# panelize.net
KiCad netlist of a schematic drawn in EAGLE
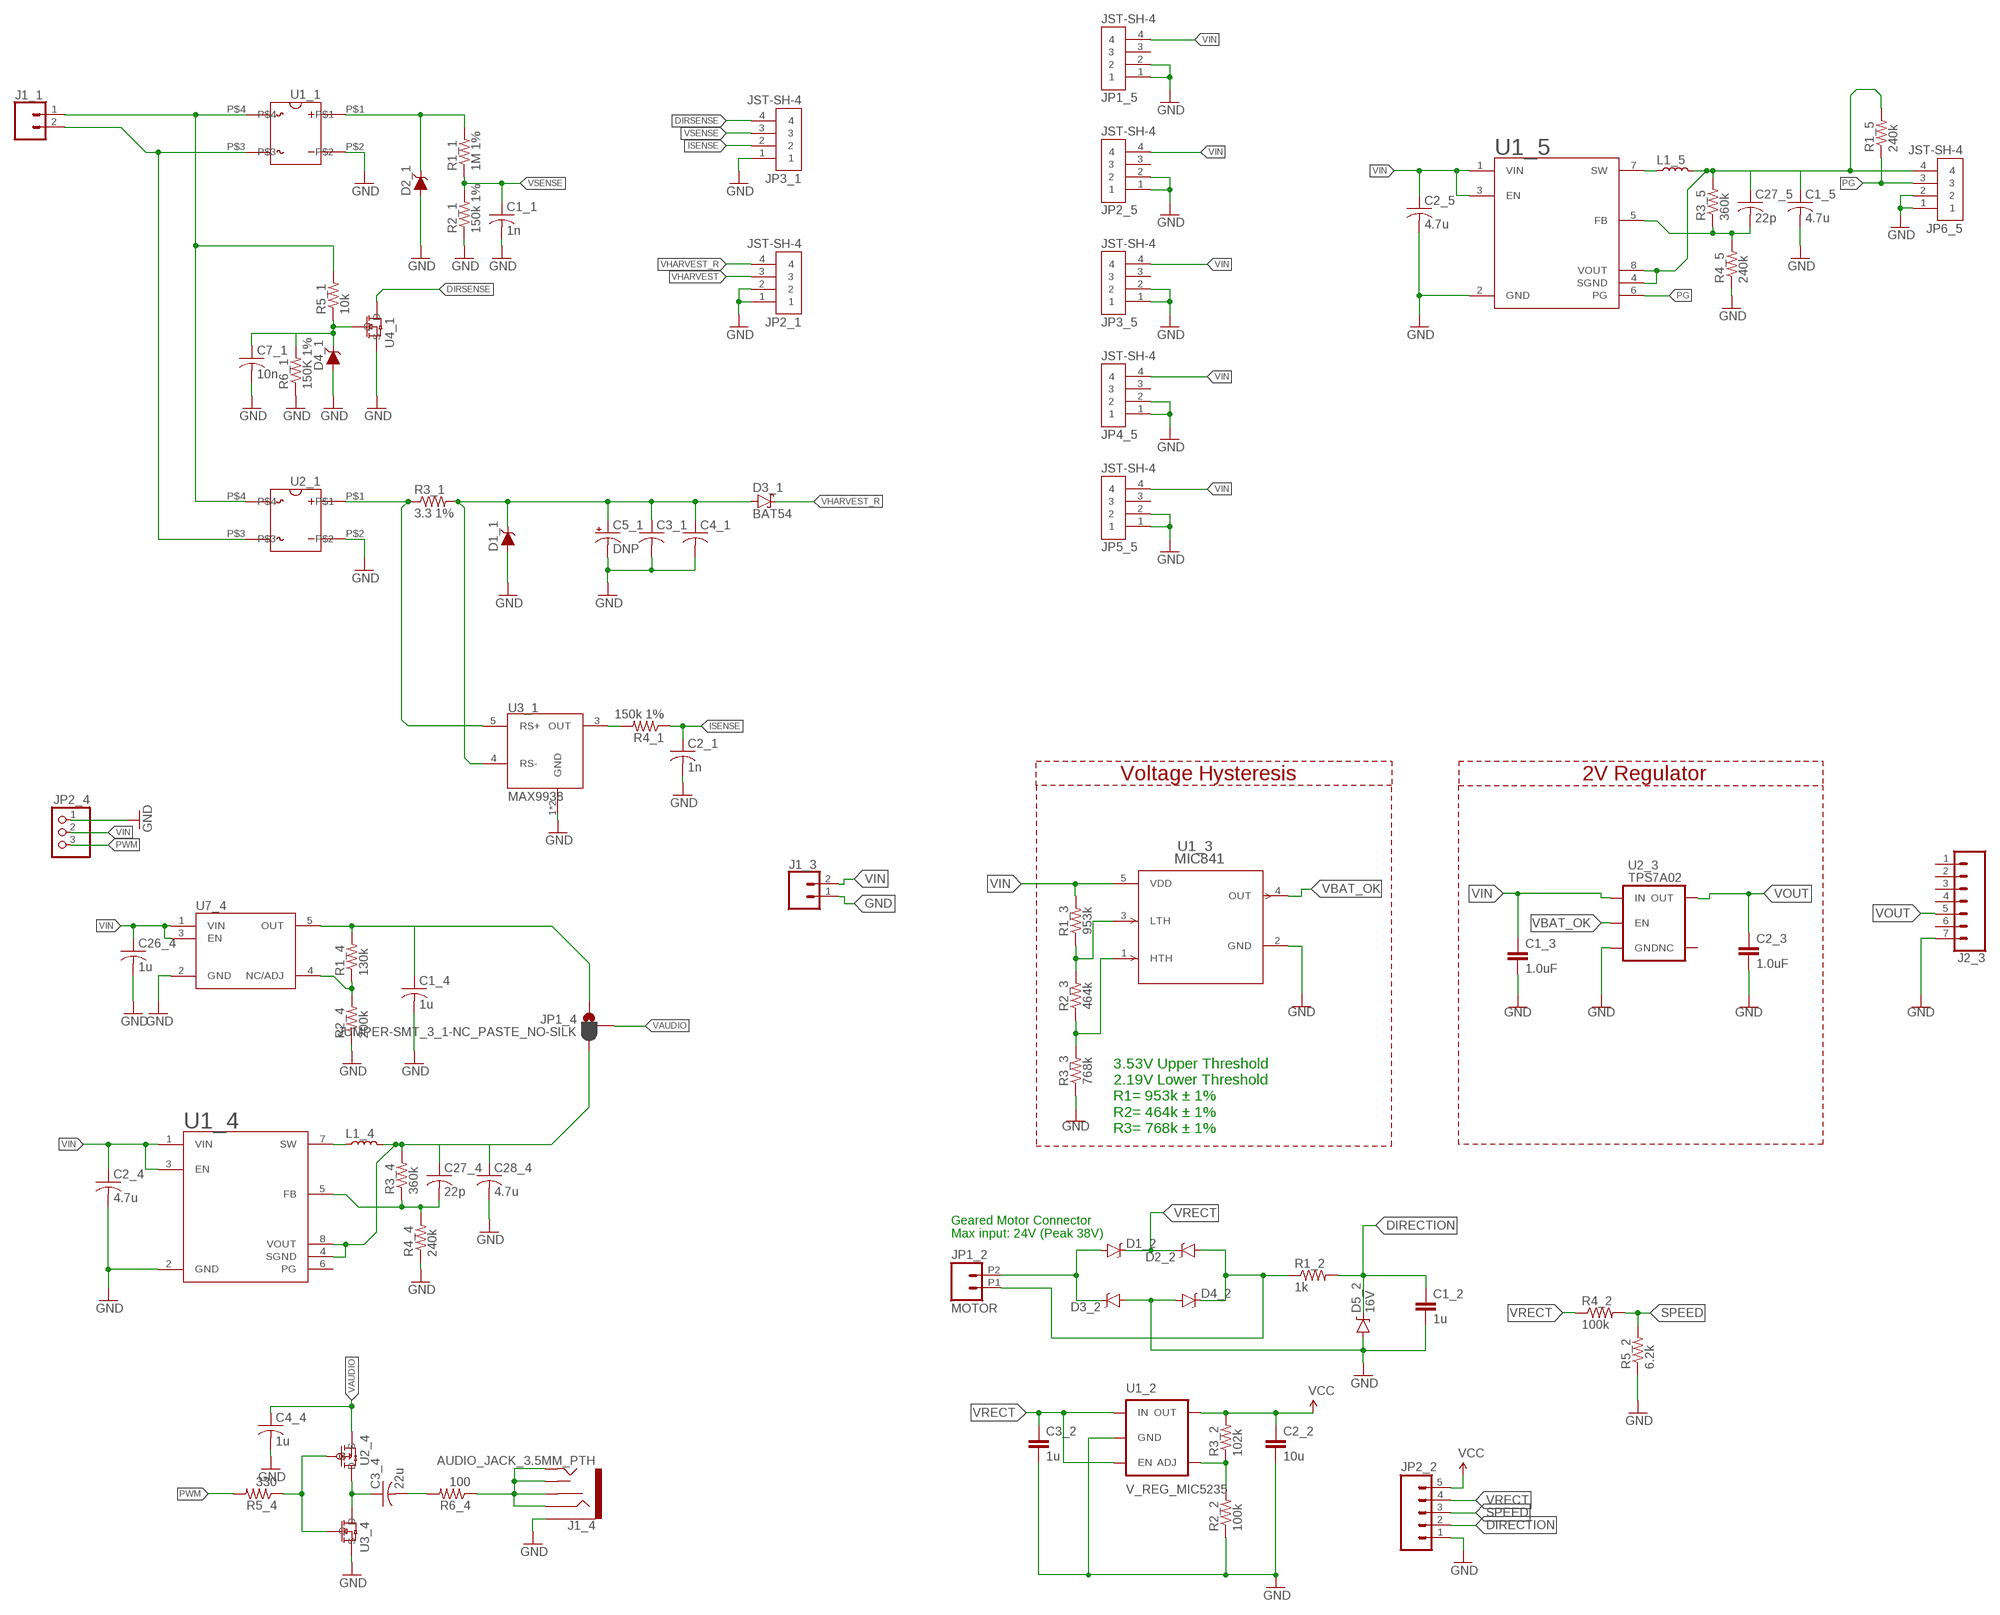
[diagram p0: schematic, sheet 1]

(export (version "E")
  (design (tool "Eeschema 10.0.6"))
  (components
    (comp (ref "C1_1")
      (value "1n")
      (footprint "eagle-import:C0402")
      (fields (field (name "MFR") "SAMSUNG"))
      (libsource (lib "eagle-import") (part "C-USC0402"))
    )
    (comp (ref "C1_2")
      (value "1u")
      (footprint "eagle-import:0805")
      (libsource (lib "eagle-import") (part "CAP0805"))
    )
    (comp (ref "C1_3")
      (value "1.0uF")
      (footprint "eagle-import:0603")
      (fields (field (name "MFR") "SAMSUNG"))
      (libsource (lib "eagle-import") (part "1.0UF-0603-16V-10%"))
    )
    (comp (ref "C1_4")
      (value "1u")
      (footprint "eagle-import:C0603")
      (fields (field (name "MFR") "SAMSUNG"))
      (libsource (lib "eagle-import") (part "C-USC0603"))
    )
    (comp (ref "C1_5")
      (value "4.7u")
      (footprint "eagle-import:C0603")
      (fields (field (name "MFR") "SAMSUNG"))
      (libsource (lib "eagle-import") (part "C-USC0603"))
    )
    (comp (ref "C2_1")
      (value "1n")
      (footprint "eagle-import:C0402")
      (fields (field (name "MFR") "SAMSUNG"))
      (libsource (lib "eagle-import") (part "C-USC0402"))
    )
    (comp (ref "C2_2")
      (value "10u")
      (footprint "eagle-import:0805")
      (libsource (lib "eagle-import") (part "CAP0805"))
    )
    (comp (ref "C2_3")
      (value "1.0uF")
      (footprint "eagle-import:0603")
      (fields (field (name "MFR") "SAMSUNG"))
      (libsource (lib "eagle-import") (part "1.0UF-0603-16V-10%"))
    )
    (comp (ref "C2_4")
      (value "4.7u")
      (footprint "eagle-import:C0603")
      (fields (field (name "MFR") "SAMSUNG"))
      (libsource (lib "eagle-import") (part "C-USC0603"))
    )
    (comp (ref "C2_5")
      (value "4.7u")
      (footprint "eagle-import:C0603")
      (fields (field (name "MFR") "SAMSUNG"))
      (libsource (lib "eagle-import") (part "C-USC0603"))
    )
    (comp (ref "C3_1")
      (value "C-USC1206")
      (footprint "eagle-import:C1206")
      (fields (field (name "MFR") "TDK"))
      (libsource (lib "eagle-import") (part "C-USC1206"))
    )
    (comp (ref "C3_2")
      (value "1u")
      (footprint "eagle-import:0805")
      (libsource (lib "eagle-import") (part "CAP0805"))
    )
    (comp (ref "C3_4")
      (value "22u")
      (footprint "eagle-import:C0805")
      (fields (field (name "MFR") "MURATA"))
      (libsource (lib "eagle-import") (part "C-USC0805"))
    )
    (comp (ref "C4_1")
      (value "C-USC1206")
      (footprint "eagle-import:C1206")
      (fields (field (name "MFR") "TDK"))
      (libsource (lib "eagle-import") (part "C-USC1206"))
    )
    (comp (ref "C4_4")
      (value "1u")
      (footprint "eagle-import:C0603")
      (fields (field (name "MFR") "SAMSUNG"))
      (libsource (lib "eagle-import") (part "C-USC0603"))
    )
    (comp (ref "C5_1")
      (value "DNP")
      (footprint "eagle-import:E2,5-5")
      (libsource (lib "eagle-import") (part "CPOL-USE2.5-5"))
    )
    (comp (ref "C7_1")
      (value "10n")
      (footprint "eagle-import:C0402")
      (fields (field (name "MFR") "SAMSUNG"))
      (libsource (lib "eagle-import") (part "C-USC0402"))
    )
    (comp (ref "C26_4")
      (value "1u")
      (footprint "eagle-import:C0603")
      (fields (field (name "MFR") "SAMSUNG"))
      (libsource (lib "eagle-import") (part "C-USC0603"))
    )
    (comp (ref "C27_4")
      (value "22p")
      (footprint "eagle-import:C0402")
      (fields (field (name "MFR") "KEMET"))
      (libsource (lib "eagle-import") (part "C-USC0402"))
    )
    (comp (ref "C27_5")
      (value "22p")
      (footprint "eagle-import:C0402")
      (fields (field (name "MFR") "KEMET"))
      (libsource (lib "eagle-import") (part "C-USC0402"))
    )
    (comp (ref "C28_4")
      (value "4.7u")
      (footprint "eagle-import:C0603")
      (fields (field (name "MFR") "SAMSUNG"))
      (libsource (lib "eagle-import") (part "C-USC0603"))
    )
    (comp (ref "D1_1")
      (value "3.3V")
      (footprint "eagle-import:SOD-323")
      (fields (field (name "MFR") "DIODES_INCORPORATED"))
      (libsource (lib "eagle-import") (part "DIODE-ZENER-MM3Z3V3T1G"))
    )
    (comp (ref "D1_2")
      (value "BAT20JFILM")
      (footprint "eagle-import:SOD-323")
      (libsource (lib "eagle-import") (part "BAT20JFILM"))
    )
    (comp (ref "D2_1")
      (value "3.3V")
      (footprint "eagle-import:SOD-323")
      (fields (field (name "MFR") "DIODES_INCORPORATED"))
      (libsource (lib "eagle-import") (part "DIODE-ZENER-MM3Z3V3T1G"))
    )
    (comp (ref "D2_2")
      (value "BAT20JFILM")
      (footprint "eagle-import:SOD-323")
      (libsource (lib "eagle-import") (part "BAT20JFILM"))
    )
    (comp (ref "D3_1")
      (value "BAT54")
      (footprint "eagle-import:SOT23")
      (fields (field (name "MFR") "ON"))
      (libsource (lib "eagle-import") (part "BAT54"))
    )
    (comp (ref "D3_2")
      (value "BAT20JFILM")
      (footprint "eagle-import:SOD-323")
      (libsource (lib "eagle-import") (part "BAT20JFILM"))
    )
    (comp (ref "D4_1")
      (value "3.3V")
      (footprint "eagle-import:SOD-323")
      (fields (field (name "MFR") "DIODES_INCORPORATED"))
      (libsource (lib "eagle-import") (part "DIODE-ZENER-MM3Z3V3T1G"))
    )
    (comp (ref "D4_2")
      (value "BAT20JFILM")
      (footprint "eagle-import:SOD-323")
      (libsource (lib "eagle-import") (part "BAT20JFILM"))
    )
    (comp (ref "D5_2")
      (value "16V")
      (footprint "eagle-import:SOD-123")
      (libsource (lib "eagle-import") (part "DIODE-ZENER16V"))
    )
    (comp (ref "J1_1")
      (value "CONN_02-JST-2MM-SMT")
      (footprint "eagle-import:JST-2-SMD")
      (fields (field (name "MFR") "JST"))
      (libsource (lib "eagle-import") (part "SparkFun-Connectors_513_CONN_02-JST-2MM-SMT"))
    )
    (comp (ref "J1_3")
      (value "CONN_02")
      (footprint "eagle-import:1X02")
      (fields (field (name "MFR") "DNP"))
      (libsource (lib "eagle-import") (part "CONN_02"))
    )
    (comp (ref "J1_4")
      (value "AUDIO_JACK_3.5MM_PTH")
      (footprint "eagle-import:AUDIO-JACK")
      (fields (field (name "MFR") "DNP"))
      (libsource (lib "eagle-import") (part "AUDIO_JACK_3.5MM_PTH"))
    )
    (comp (ref "J2_3")
      (value "CONN_07")
      (footprint "eagle-import:1X07")
      (fields (field (name "MFR") "DNP"))
      (libsource (lib "eagle-import") (part "CONN_07"))
    )
    (comp (ref "JP1_2")
      (value "MOTOR")
      (footprint "eagle-import:1X02_2.54_SCREWTERM@1")
      (fields (field (name "MFR") "DNP"))
      (libsource (lib "eagle-import") (part "M022.54MM_SCREWTERM"))
    )
    (comp (ref "JP1_4")
      (value "JUMPER-SMT_3_1-NC_PASTE_NO-SILK")
      (footprint "eagle-import:SMT-JUMPER_3_1-NC_PASTE_NO-SILK")
      (fields (field (name "MFR") "DNP"))
      (libsource (lib "eagle-import") (part "JUMPER-SMT_3_1-NC_PASTE_NO-SILK"))
    )
    (comp (ref "JP1_5")
      (value "JST-SH-4")
      (footprint "eagle-import:JST-SH-4")
      (fields (field (name "MFR") "JST"))
      (libsource (lib "eagle-import") (part "JST-SH-4"))
    )
    (comp (ref "JP2_1")
      (value "JST-SH-4")
      (footprint "eagle-import:JST-SH-4")
      (fields (field (name "MFR") "JST"))
      (libsource (lib "eagle-import") (part "JST-SH-4"))
    )
    (comp (ref "JP2_2")
      (value "M05LOCK")
      (footprint "eagle-import:1X05_LOCK")
      (fields (field (name "MFR") "DNP"))
      (libsource (lib "eagle-import") (part "M05LOCK"))
    )
    (comp (ref "JP2_4")
      (value "PINHD-1X3")
      (footprint "eagle-import:1X03")
      (fields (field (name "MFR") "DNP"))
      (libsource (lib "eagle-import") (part "PINHD-1X3"))
    )
    (comp (ref "JP2_5")
      (value "JST-SH-4")
      (footprint "eagle-import:JST-SH-4")
      (fields (field (name "MFR") "JST"))
      (libsource (lib "eagle-import") (part "JST-SH-4"))
    )
    (comp (ref "JP3_1")
      (value "JST-SH-4")
      (footprint "eagle-import:JST-SH-4")
      (fields (field (name "MFR") "JST"))
      (libsource (lib "eagle-import") (part "JST-SH-4"))
    )
    (comp (ref "JP3_5")
      (value "JST-SH-4")
      (footprint "eagle-import:JST-SH-4")
      (fields (field (name "MFR") "JST"))
      (libsource (lib "eagle-import") (part "JST-SH-4"))
    )
    (comp (ref "JP4_5")
      (value "JST-SH-4")
      (footprint "eagle-import:JST-SH-4")
      (fields (field (name "MFR") "JST"))
      (libsource (lib "eagle-import") (part "JST-SH-4"))
    )
    (comp (ref "JP5_5")
      (value "JST-SH-4")
      (footprint "eagle-import:JST-SH-4")
      (fields (field (name "MFR") "JST"))
      (libsource (lib "eagle-import") (part "JST-SH-4"))
    )
    (comp (ref "JP6_5")
      (value "JST-SH-4")
      (footprint "eagle-import:JST-SH-4")
      (fields (field (name "MFR") "JST"))
      (libsource (lib "eagle-import") (part "JST-SH-4"))
    )
    (comp (ref "L1_4")
      (value "22u")
      (footprint "eagle-import:LQH3NPNXXXXMEX")
      (fields (field (name "MFR") "MURATA"))
      (libsource (lib "eagle-import") (part "LQH3NPN220MMEL"))
    )
    (comp (ref "L1_5")
      (value "22u")
      (footprint "eagle-import:LQH3NPNXXXXMEX")
      (fields (field (name "MFR") "MURATA"))
      (libsource (lib "eagle-import") (part "LQH3NPN220MMEL"))
    )
    (comp (ref "R1_1")
      (value "1M 1%")
      (footprint "eagle-import:R0402")
      (fields (field (name "MFR") "YAGEO"))
      (libsource (lib "eagle-import") (part "R-US_R0402"))
    )
    (comp (ref "R1_2")
      (value "1k")
      (footprint "eagle-import:0805")
      (fields (field (name "MFR") "YAGEO"))
      (libsource (lib "eagle-import") (part "RESISTOR0805-RES"))
    )
    (comp (ref "R1_3")
      (value "953k")
      (footprint "eagle-import:0603")
      (fields (field (name "MFR") "PANASONIC"))
      (libsource (lib "eagle-import") (part "RESISTOR0603"))
    )
    (comp (ref "R1_4")
      (value "130k")
      (footprint "eagle-import:R0603")
      (fields (field (name "MFR") "PANASONIC"))
      (libsource (lib "eagle-import") (part "R-US_R0603"))
    )
    (comp (ref "R1_5")
      (value "240k")
      (footprint "eagle-import:R0603")
      (fields (field (name "MFR") "PANASONIC"))
      (libsource (lib "eagle-import") (part "R-US_R0603"))
    )
    (comp (ref "R2_1")
      (value "150k 1%")
      (footprint "eagle-import:R0402")
      (fields (field (name "MFR") "YAGEO"))
      (libsource (lib "eagle-import") (part "R-US_R0402"))
    )
    (comp (ref "R2_2")
      (value "100k")
      (footprint "eagle-import:0805")
      (fields (field (name "MFR") "YAGEO"))
      (libsource (lib "eagle-import") (part "RESISTOR0805-RES"))
    )
    (comp (ref "R2_3")
      (value "464k")
      (footprint "eagle-import:0603")
      (fields (field (name "MFR") "PANASONIC"))
      (libsource (lib "eagle-import") (part "RESISTOR0603"))
    )
    (comp (ref "R2_4")
      (value "200k")
      (footprint "eagle-import:R0603")
      (fields (field (name "MFR") "PANASONIC"))
      (libsource (lib "eagle-import") (part "R-US_R0603"))
    )
    (comp (ref "R3_1")
      (value "3.3 1%")
      (footprint "eagle-import:R0603")
      (fields (field (name "MFR") "PANASONIC"))
      (libsource (lib "eagle-import") (part "R-US_R0603"))
    )
    (comp (ref "R3_2")
      (value "102k")
      (footprint "eagle-import:0805")
      (fields (field (name "MFR") "YAGEO"))
      (libsource (lib "eagle-import") (part "RESISTOR0805-RES"))
    )
    (comp (ref "R3_3")
      (value "768k")
      (footprint "eagle-import:0603")
      (fields (field (name "MFR") "PANASONIC"))
      (libsource (lib "eagle-import") (part "RESISTOR0603"))
    )
    (comp (ref "R3_4")
      (value "360k")
      (footprint "eagle-import:R0603")
      (fields (field (name "MFR") "PANASONIC"))
      (libsource (lib "eagle-import") (part "R-US_R0603"))
    )
    (comp (ref "R3_5")
      (value "360k")
      (footprint "eagle-import:R0603")
      (fields (field (name "MFR") "PANASONIC"))
      (libsource (lib "eagle-import") (part "R-US_R0603"))
    )
    (comp (ref "R4_1")
      (value "150k 1%")
      (footprint "eagle-import:R0402")
      (fields (field (name "MFR") "YAGEO"))
      (libsource (lib "eagle-import") (part "R-US_R0402"))
    )
    (comp (ref "R4_2")
      (value "100k")
      (footprint "eagle-import:0805")
      (fields (field (name "MFR") "YAGEO"))
      (libsource (lib "eagle-import") (part "RESISTOR0805-RES"))
    )
    (comp (ref "R4_4")
      (value "240k")
      (footprint "eagle-import:R0603")
      (fields (field (name "MFR") "PANASONIC"))
      (libsource (lib "eagle-import") (part "R-US_R0603"))
    )
    (comp (ref "R4_5")
      (value "240k")
      (footprint "eagle-import:R0603")
      (fields (field (name "MFR") "PANASONIC"))
      (libsource (lib "eagle-import") (part "R-US_R0603"))
    )
    (comp (ref "R5_1")
      (value "10k")
      (footprint "eagle-import:R0402")
      (fields (field (name "MFR") "YAGEO"))
      (libsource (lib "eagle-import") (part "R-US_R0402"))
    )
    (comp (ref "R5_2")
      (value "6.2k")
      (footprint "eagle-import:0805")
      (fields (field (name "MFR") "YAGEO"))
      (libsource (lib "eagle-import") (part "RESISTOR0805-RES"))
    )
    (comp (ref "R5_4")
      (value "330")
      (footprint "eagle-import:R0603")
      (fields (field (name "MFR") "YAGEO"))
      (libsource (lib "eagle-import") (part "R-US_R0603"))
    )
    (comp (ref "R6_1")
      (value "150K 1%")
      (footprint "eagle-import:R0402")
      (fields (field (name "MFR") "YAGEO"))
      (libsource (lib "eagle-import") (part "R-US_R0402"))
    )
    (comp (ref "R6_4")
      (value "100")
      (footprint "eagle-import:R0603")
      (fields (field (name "MFR") "YAGEO"))
      (libsource (lib "eagle-import") (part "R-US_R0603"))
    )
    (comp (ref "U1_1")
      (value "CDBHD140L-G")
      (footprint "eagle-import:CDBHDXX0L-G")
      (fields (field (name "MFR") "COMCHIP"))
      (libsource (lib "eagle-import") (part "CDBHD140L-G"))
    )
    (comp (ref "U1_2")
      (value "V_REG_MIC5235")
      (footprint "eagle-import:SOT23-5")
      (libsource (lib "eagle-import") (part "V_REG_MIC5235"))
    )
    (comp (ref "U1_3")
      (value "MIC841")
      (footprint "eagle-import:SC-70_C5_MCH")
      (fields
        (field (name "MANUFACTURER_PART_NUMBER") "MIC841NYC5-TR")
        (field (name "COPYRIGHT") "Copyright (C) 2018 Accelerated Designs. All rights reserved")
      )
      (libsource (lib "eagle-import") (part "MIC841HYC5-TR"))
    )
    (comp (ref "U1_4")
      (value "TPS62120")
      (footprint "eagle-import:SOP65P280X145-8N")
      (fields (field (name "MFR") "TI"))
      (libsource (lib "eagle-import") (part "TPS62120"))
    )
    (comp (ref "U1_5")
      (value "TPS62120")
      (footprint "eagle-import:SOP65P280X145-8N")
      (fields (field (name "MFR") "TI"))
      (libsource (lib "eagle-import") (part "TPS62120"))
    )
    (comp (ref "U2_1")
      (value "CDBHD140L-G")
      (footprint "eagle-import:CDBHDXX0L-G")
      (fields (field (name "MFR") "COMCHIP"))
      (libsource (lib "eagle-import") (part "CDBHD140L-G"))
    )
    (comp (ref "U2_3")
      (value "TPS7A02")
      (footprint "eagle-import:SOT23-5")
      (fields (field (name "MFR") "TI"))
      (libsource (lib "eagle-import") (part "TPS7A02"))
    )
    (comp (ref "U2_4")
      (value "TP2104K1-G")
      (footprint "eagle-import:TP2104K1-G")
      (fields (field (name "MFR") "MICROCHIP"))
      (libsource (lib "eagle-import") (part "TP2104K1-G"))
    )
    (comp (ref "U3_1")
      (value "MAX9938")
      (footprint "eagle-import:SOT23-5")
      (fields (field (name "MFR") "MAXIM"))
      (libsource (lib "eagle-import") (part "MAX9938"))
    )
    (comp (ref "U3_4")
      (value "TN2106K1-G")
      (footprint "eagle-import:TN2106K1-G")
      (fields (field (name "MFR") "MICROCHIP"))
      (libsource (lib "eagle-import") (part "TN2106K1-G"))
    )
    (comp (ref "U4_1")
      (value "TN2106K1-G")
      (footprint "eagle-import:TN2106K1-G")
      (fields (field (name "MFR") "MICROCHIP"))
      (libsource (lib "eagle-import") (part "TN2106K1-G"))
    )
    (comp (ref "U7_4")
      (value "MIC5225")
      (footprint "eagle-import:MIC5225")
      (fields (field (name "MFR") "MICROCHIP"))
      (libsource (lib "eagle-import") (part "MIC5225"))
    )
  )
  (nets
    (net (code "1") (name "DIRECTION") (class "Default")
      (node (ref "C1_2") (pin "1") (pinfunction "1_1") (pintype "passive"))
      (node (ref "D5_2") (pin "C") (pinfunction "C_C") (pintype "passive"))
      (node (ref "JP2_2") (pin "2") (pinfunction "2_2") (pintype "passive"))
      (node (ref "R1_2") (pin "2") (pinfunction "2_2") (pintype "passive"))
    )
    (net (code "2") (name "DIRSENSE") (class "Default")
      (node (ref "JP3_1") (pin "4") (pinfunction "4_4") (pintype "bidirectional"))
      (node (ref "U4_1") (pin "D") (pinfunction "D_D") (pintype "bidirectional"))
    )
    (net (code "3") (name "GND") (class "Default")
      (node (ref "C1_1") (pin "2") (pinfunction "2_2") (pintype "passive"))
      (node (ref "C1_2") (pin "2") (pinfunction "2_2") (pintype "passive"))
      (node (ref "C1_3") (pin "2") (pinfunction "2_2") (pintype "passive"))
      (node (ref "C1_4") (pin "2") (pinfunction "2_2") (pintype "passive"))
      (node (ref "C1_5") (pin "2") (pinfunction "2_2") (pintype "passive"))
      (node (ref "C26_4") (pin "2") (pinfunction "2_2") (pintype "passive"))
      (node (ref "C28_4") (pin "2") (pinfunction "2_2") (pintype "passive"))
      (node (ref "C2_1") (pin "2") (pinfunction "2_2") (pintype "passive"))
      (node (ref "C2_2") (pin "2") (pinfunction "2_2") (pintype "passive"))
      (node (ref "C2_3") (pin "2") (pinfunction "2_2") (pintype "passive"))
      (node (ref "C2_4") (pin "2") (pinfunction "2_2") (pintype "passive"))
      (node (ref "C2_5") (pin "2") (pinfunction "2_2") (pintype "passive"))
      (node (ref "C3_1") (pin "2") (pinfunction "2_2") (pintype "passive"))
      (node (ref "C3_2") (pin "2") (pinfunction "2_2") (pintype "passive"))
      (node (ref "C4_1") (pin "2") (pinfunction "2_2") (pintype "passive"))
      (node (ref "C4_4") (pin "2") (pinfunction "2_2") (pintype "passive"))
      (node (ref "C5_1") (pin "-") (pinfunction "-_-") (pintype "passive"))
      (node (ref "C7_1") (pin "2") (pinfunction "2_2") (pintype "passive"))
      (node (ref "D1_1") (pin "A") (pinfunction "A_A") (pintype "passive"))
      (node (ref "D2_1") (pin "A") (pinfunction "A_A") (pintype "passive"))
      (node (ref "D3_2") (pin "A") (pinfunction "A_A") (pintype "passive"))
      (node (ref "D4_1") (pin "A") (pinfunction "A_A") (pintype "passive"))
      (node (ref "D4_2") (pin "A") (pinfunction "A_A") (pintype "passive"))
      (node (ref "D5_2") (pin "A") (pinfunction "A_A") (pintype "passive"))
      (node (ref "J1_3") (pin "1") (pinfunction "1_1") (pintype "passive"))
      (node (ref "J1_4") (pin "SLEEVE") (pinfunction "SLEEVE_SLEEVE") (pintype "bidirectional"))
      (node (ref "J2_3") (pin "7") (pinfunction "7_7") (pintype "passive"))
      (node (ref "JP1_5") (pin "1") (pinfunction "1_1") (pintype "bidirectional"))
      (node (ref "JP1_5") (pin "2") (pinfunction "2_2") (pintype "bidirectional"))
      (node (ref "JP2_1") (pin "1") (pinfunction "1_1") (pintype "bidirectional"))
      (node (ref "JP2_1") (pin "2") (pinfunction "2_2") (pintype "bidirectional"))
      (node (ref "JP2_2") (pin "1") (pinfunction "1_1") (pintype "passive"))
      (node (ref "JP2_4") (pin "1") (pinfunction "1_1") (pintype "passive"))
      (node (ref "JP2_5") (pin "1") (pinfunction "1_1") (pintype "bidirectional"))
      (node (ref "JP2_5") (pin "2") (pinfunction "2_2") (pintype "bidirectional"))
      (node (ref "JP3_1") (pin "1") (pinfunction "1_1") (pintype "bidirectional"))
      (node (ref "JP3_5") (pin "1") (pinfunction "1_1") (pintype "bidirectional"))
      (node (ref "JP3_5") (pin "2") (pinfunction "2_2") (pintype "bidirectional"))
      (node (ref "JP4_5") (pin "1") (pinfunction "1_1") (pintype "bidirectional"))
      (node (ref "JP4_5") (pin "2") (pinfunction "2_2") (pintype "bidirectional"))
      (node (ref "JP5_5") (pin "1") (pinfunction "1_1") (pintype "bidirectional"))
      (node (ref "JP5_5") (pin "2") (pinfunction "2_2") (pintype "bidirectional"))
      (node (ref "JP6_5") (pin "1") (pinfunction "1_1") (pintype "bidirectional"))
      (node (ref "JP6_5") (pin "2") (pinfunction "2_2") (pintype "bidirectional"))
      (node (ref "R2_1") (pin "1") (pinfunction "1_1") (pintype "passive"))
      (node (ref "R2_2") (pin "1") (pinfunction "1_1") (pintype "passive"))
      (node (ref "R2_4") (pin "1") (pinfunction "1_1") (pintype "passive"))
      (node (ref "R3_3") (pin "1") (pinfunction "1_1") (pintype "passive"))
      (node (ref "R4_4") (pin "1") (pinfunction "1_1") (pintype "passive"))
      (node (ref "R4_5") (pin "1") (pinfunction "1_1") (pintype "passive"))
      (node (ref "R5_2") (pin "1") (pinfunction "1_1") (pintype "passive"))
      (node (ref "R6_1") (pin "1") (pinfunction "1_1") (pintype "passive"))
      (node (ref "U1_1") (pin "P$2") (pinfunction "P$2_P$2") (pintype "bidirectional"))
      (node (ref "U1_2") (pin "2") (pinfunction "GND_2") (pintype "input"))
      (node (ref "U1_3") (pin "2") (pinfunction "GND_2") (pintype "power_in"))
      (node (ref "U1_4") (pin "2") (pinfunction "GND_2") (pintype "bidirectional"))
      (node (ref "U1_5") (pin "2") (pinfunction "GND_2") (pintype "bidirectional"))
      (node (ref "U2_1") (pin "P$2") (pinfunction "P$2_P$2") (pintype "bidirectional"))
      (node (ref "U2_3") (pin "2") (pinfunction "GND_2") (pintype "input"))
      (node (ref "U3_1") (pin "1") (pinfunction "GND_1") (pintype "bidirectional"))
      (node (ref "U3_1") (pin "2") (pinfunction "GND_2") (pintype "bidirectional"))
      (node (ref "U3_4") (pin "S") (pinfunction "S_S") (pintype "bidirectional"))
      (node (ref "U4_1") (pin "S") (pinfunction "S_S") (pintype "bidirectional"))
      (node (ref "U7_4") (pin "2") (pinfunction "GND_2") (pintype "bidirectional"))
    )
    (net (code "4") (name "ISENSE") (class "Default")
      (node (ref "C2_1") (pin "1") (pinfunction "1_1") (pintype "passive"))
      (node (ref "JP3_1") (pin "2") (pinfunction "2_2") (pintype "bidirectional"))
      (node (ref "R4_1") (pin "1") (pinfunction "1_1") (pintype "passive"))
    )
    (net (code "5") (name "Net-(C3_4-Pad1)") (class "Default")
      (node (ref "C3_4") (pin "1") (pinfunction "1_1") (pintype "passive"))
      (node (ref "U2_4") (pin "D") (pinfunction "D_D") (pintype "bidirectional"))
      (node (ref "U3_4") (pin "D") (pinfunction "D_D") (pintype "bidirectional"))
    )
    (net (code "6") (name "Net-(C3_4-Pad2)") (class "Default")
      (node (ref "C3_4") (pin "2") (pinfunction "2_2") (pintype "passive"))
      (node (ref "R6_4") (pin "2") (pinfunction "2_2") (pintype "passive"))
    )
    (net (code "7") (name "Net-(C7_1-Pad1)") (class "Default")
      (node (ref "C7_1") (pin "1") (pinfunction "1_1") (pintype "passive"))
      (node (ref "D4_1") (pin "C") (pinfunction "C_C") (pintype "passive"))
      (node (ref "R5_1") (pin "1") (pinfunction "1_1") (pintype "passive"))
      (node (ref "R6_1") (pin "2") (pinfunction "2_2") (pintype "passive"))
      (node (ref "U4_1") (pin "G") (pinfunction "G_G") (pintype "bidirectional"))
    )
    (net (code "8") (name "Net-(D2_1-PadC)") (class "Default")
      (node (ref "D2_1") (pin "C") (pinfunction "C_C") (pintype "passive"))
      (node (ref "R1_1") (pin "2") (pinfunction "2_2") (pintype "passive"))
      (node (ref "U1_1") (pin "P$1") (pinfunction "P$1_P$1") (pintype "bidirectional"))
    )
    (net (code "9") (name "Net-(J1_1-1)") (class "Default")
      (node (ref "J1_1") (pin "2") (pinfunction "1_2") (pintype "passive"))
      (node (ref "U1_1") (pin "P$3") (pinfunction "P$3_P$3") (pintype "bidirectional"))
      (node (ref "U2_1") (pin "P$3") (pinfunction "P$3_P$3") (pintype "bidirectional"))
    )
    (net (code "10") (name "Net-(J1_1-2)") (class "Default")
      (node (ref "J1_1") (pin "1") (pinfunction "2_1") (pintype "passive"))
      (node (ref "R5_1") (pin "2") (pinfunction "2_2") (pintype "passive"))
      (node (ref "U1_1") (pin "P$4") (pinfunction "P$4_P$4") (pintype "bidirectional"))
      (node (ref "U2_1") (pin "P$4") (pinfunction "P$4_P$4") (pintype "bidirectional"))
    )
    (net (code "11") (name "Net-(J1_4-PadRING)") (class "Default")
      (node (ref "J1_4") (pin "RING") (pinfunction "RING_RING") (pintype "bidirectional"))
      (node (ref "J1_4") (pin "RSH") (pinfunction "RSH_RSH") (pintype "bidirectional"))
      (node (ref "J1_4") (pin "TIP") (pinfunction "TIP_TIP") (pintype "bidirectional"))
      (node (ref "J1_4") (pin "TSH") (pinfunction "TSH_TSH") (pintype "bidirectional"))
      (node (ref "R6_4") (pin "1") (pinfunction "1_1") (pintype "passive"))
    )
    (net (code "12") (name "Net-(JP1_2-1)") (class "Default")
      (node (ref "D2_2") (pin "A") (pinfunction "A_A") (pintype "passive"))
      (node (ref "D4_2") (pin "C") (pinfunction "C_C") (pintype "passive"))
      (node (ref "JP1_2") (pin "P1") (pinfunction "1_P1") (pintype "passive"))
      (node (ref "R1_2") (pin "1") (pinfunction "1_1") (pintype "passive"))
    )
    (net (code "13") (name "Net-(JP1_2-2)") (class "Default")
      (node (ref "D1_2") (pin "A") (pinfunction "A_A") (pintype "passive"))
      (node (ref "D3_2") (pin "C") (pinfunction "C_C") (pintype "passive"))
      (node (ref "JP1_2") (pin "P2") (pinfunction "2_P2") (pintype "passive"))
    )
    (net (code "14") (name "Net-(R5_4-Pad1)") (class "Default")
      (node (ref "R5_4") (pin "1") (pinfunction "1_1") (pintype "passive"))
      (node (ref "U2_4") (pin "G") (pinfunction "G_G") (pintype "bidirectional"))
      (node (ref "U3_4") (pin "G") (pinfunction "G_G") (pintype "bidirectional"))
    )
    (net (code "15") (name "Net-(U1_2-ADJ)") (class "Default")
      (node (ref "R2_2") (pin "2") (pinfunction "2_2") (pintype "passive"))
      (node (ref "R3_2") (pin "1") (pinfunction "1_1") (pintype "passive"))
      (node (ref "U1_2") (pin "4") (pinfunction "ADJ_4") (pintype "input"))
    )
    (net (code "16") (name "Net-(U1_3-HTH)") (class "Default")
      (node (ref "R2_3") (pin "1") (pinfunction "1_1") (pintype "passive"))
      (node (ref "R3_3") (pin "2") (pinfunction "2_2") (pintype "passive"))
      (node (ref "U1_3") (pin "1") (pinfunction "HTH_1") (pintype "input"))
    )
    (net (code "17") (name "Net-(U1_3-LTH)") (class "Default")
      (node (ref "R1_3") (pin "1") (pinfunction "1_1") (pintype "passive"))
      (node (ref "R2_3") (pin "2") (pinfunction "2_2") (pintype "passive"))
      (node (ref "U1_3") (pin "3") (pinfunction "LTH_3") (pintype "input"))
    )
    (net (code "18") (name "Net-(U1_4-FB)") (class "Default")
      (node (ref "C27_4") (pin "2") (pinfunction "2_2") (pintype "passive"))
      (node (ref "R3_4") (pin "1") (pinfunction "1_1") (pintype "passive"))
      (node (ref "R4_4") (pin "2") (pinfunction "2_2") (pintype "passive"))
      (node (ref "U1_4") (pin "5") (pinfunction "FB_5") (pintype "bidirectional"))
    )
    (net (code "19") (name "Net-(U1_4-SGND)") (class "Default")
      (node (ref "C27_4") (pin "1") (pinfunction "1_1") (pintype "passive"))
      (node (ref "C28_4") (pin "1") (pinfunction "1_1") (pintype "passive"))
      (node (ref "JP1_4") (pin "3") (pinfunction "3_3") (pintype "passive"))
      (node (ref "L1_4") (pin "P$2") (pinfunction "P$2_P$2") (pintype "bidirectional"))
      (node (ref "R3_4") (pin "2") (pinfunction "2_2") (pintype "passive"))
      (node (ref "U1_4") (pin "4") (pinfunction "SGND_4") (pintype "bidirectional"))
      (node (ref "U1_4") (pin "8") (pinfunction "VOUT_8") (pintype "bidirectional"))
    )
    (net (code "20") (name "Net-(U1_4-SW)") (class "Default")
      (node (ref "L1_4") (pin "P$1") (pinfunction "P$1_P$1") (pintype "bidirectional"))
      (node (ref "U1_4") (pin "7") (pinfunction "SW_7") (pintype "bidirectional"))
    )
    (net (code "21") (name "Net-(U1_5-FB)") (class "Default")
      (node (ref "C27_5") (pin "2") (pinfunction "2_2") (pintype "passive"))
      (node (ref "R3_5") (pin "1") (pinfunction "1_1") (pintype "passive"))
      (node (ref "R4_5") (pin "2") (pinfunction "2_2") (pintype "passive"))
      (node (ref "U1_5") (pin "5") (pinfunction "FB_5") (pintype "bidirectional"))
    )
    (net (code "22") (name "Net-(U1_5-SGND)") (class "Default")
      (node (ref "C1_5") (pin "1") (pinfunction "1_1") (pintype "passive"))
      (node (ref "C27_5") (pin "1") (pinfunction "1_1") (pintype "passive"))
      (node (ref "JP6_5") (pin "4") (pinfunction "4_4") (pintype "bidirectional"))
      (node (ref "L1_5") (pin "P$2") (pinfunction "P$2_P$2") (pintype "bidirectional"))
      (node (ref "R1_5") (pin "2") (pinfunction "2_2") (pintype "passive"))
      (node (ref "R3_5") (pin "2") (pinfunction "2_2") (pintype "passive"))
      (node (ref "U1_5") (pin "4") (pinfunction "SGND_4") (pintype "bidirectional"))
      (node (ref "U1_5") (pin "8") (pinfunction "VOUT_8") (pintype "bidirectional"))
    )
    (net (code "23") (name "Net-(U1_5-SW)") (class "Default")
      (node (ref "L1_5") (pin "P$1") (pinfunction "P$1_P$1") (pintype "bidirectional"))
      (node (ref "U1_5") (pin "7") (pinfunction "SW_7") (pintype "bidirectional"))
    )
    (net (code "24") (name "Net-(U3_1-OUT)") (class "Default")
      (node (ref "R4_1") (pin "2") (pinfunction "2_2") (pintype "passive"))
      (node (ref "U3_1") (pin "3") (pinfunction "OUT_3") (pintype "bidirectional"))
    )
    (net (code "25") (name "Net-(U3_1-RS+)") (class "Default")
      (node (ref "R3_1") (pin "1") (pinfunction "1_1") (pintype "passive"))
      (node (ref "U2_1") (pin "P$1") (pinfunction "P$1_P$1") (pintype "bidirectional"))
      (node (ref "U3_1") (pin "5") (pinfunction "RS+_5") (pintype "bidirectional"))
    )
    (net (code "26") (name "Net-(U7_4-NC{slash}ADJ)") (class "Default")
      (node (ref "R1_4") (pin "1") (pinfunction "1_1") (pintype "passive"))
      (node (ref "R2_4") (pin "2") (pinfunction "2_2") (pintype "passive"))
      (node (ref "U7_4") (pin "4") (pinfunction "NC/ADJ_4") (pintype "bidirectional"))
    )
    (net (code "27") (name "Net-(U7_4-OUT)") (class "Default")
      (node (ref "C1_4") (pin "1") (pinfunction "1_1") (pintype "passive"))
      (node (ref "JP1_4") (pin "1") (pinfunction "1_1") (pintype "passive"))
      (node (ref "R1_4") (pin "2") (pinfunction "2_2") (pintype "passive"))
      (node (ref "U7_4") (pin "5") (pinfunction "OUT_5") (pintype "bidirectional"))
    )
    (net (code "28") (name "PG") (class "Default")
      (node (ref "JP6_5") (pin "3") (pinfunction "3_3") (pintype "bidirectional"))
      (node (ref "R1_5") (pin "1") (pinfunction "1_1") (pintype "passive"))
      (node (ref "U1_5") (pin "6") (pinfunction "PG_6") (pintype "bidirectional"))
    )
    (net (code "29") (name "PWM") (class "Default")
      (node (ref "JP2_4") (pin "3") (pinfunction "3_3") (pintype "passive"))
      (node (ref "R5_4") (pin "2") (pinfunction "2_2") (pintype "passive"))
    )
    (net (code "30") (name "SPEED") (class "Default")
      (node (ref "JP2_2") (pin "3") (pinfunction "3_3") (pintype "passive"))
      (node (ref "R4_2") (pin "2") (pinfunction "2_2") (pintype "passive"))
      (node (ref "R5_2") (pin "2") (pinfunction "2_2") (pintype "passive"))
    )
    (net (code "31") (name "VAUDIO") (class "Default")
      (node (ref "C4_4") (pin "1") (pinfunction "1_1") (pintype "passive"))
      (node (ref "JP1_4") (pin "2") (pinfunction "2_2") (pintype "passive"))
      (node (ref "U2_4") (pin "S") (pinfunction "S_S") (pintype "bidirectional"))
    )
    (net (code "32") (name "VBAT_OK") (class "Default")
      (node (ref "U1_3") (pin "4") (pinfunction "OUT_4") (pintype "output"))
      (node (ref "U2_3") (pin "3") (pinfunction "EN_3") (pintype "input"))
    )
    (net (code "33") (name "VCC") (class "Default")
      (node (ref "C2_2") (pin "1") (pinfunction "1_1") (pintype "passive"))
      (node (ref "JP2_2") (pin "5") (pinfunction "5_5") (pintype "passive"))
      (node (ref "R3_2") (pin "2") (pinfunction "2_2") (pintype "passive"))
      (node (ref "U1_2") (pin "5") (pinfunction "OUT_5") (pintype "passive"))
    )
    (net (code "34") (name "VHARVEST") (class "Default")
      (node (ref "C3_1") (pin "1") (pinfunction "1_1") (pintype "passive"))
      (node (ref "C4_1") (pin "1") (pinfunction "1_1") (pintype "passive"))
      (node (ref "C5_1") (pin "+") (pinfunction "+_+") (pintype "passive"))
      (node (ref "D1_1") (pin "C") (pinfunction "C_C") (pintype "passive"))
      (node (ref "D3_1") (pin "1") (pinfunction "A_1") (pintype "passive"))
      (node (ref "JP2_1") (pin "3") (pinfunction "3_3") (pintype "bidirectional"))
      (node (ref "R3_1") (pin "2") (pinfunction "2_2") (pintype "passive"))
      (node (ref "U3_1") (pin "4") (pinfunction "RS-_4") (pintype "bidirectional"))
    )
    (net (code "35") (name "VHARVEST_R") (class "Default")
      (node (ref "D3_1") (pin "3") (pinfunction "C_3") (pintype "passive"))
      (node (ref "JP2_1") (pin "4") (pinfunction "4_4") (pintype "bidirectional"))
    )
    (net (code "36") (name "VIN") (class "Default")
      (node (ref "C1_3") (pin "1") (pinfunction "1_1") (pintype "passive"))
      (node (ref "C26_4") (pin "1") (pinfunction "1_1") (pintype "passive"))
      (node (ref "C2_4") (pin "1") (pinfunction "1_1") (pintype "passive"))
      (node (ref "C2_5") (pin "1") (pinfunction "1_1") (pintype "passive"))
      (node (ref "J1_3") (pin "2") (pinfunction "2_2") (pintype "passive"))
      (node (ref "JP1_5") (pin "4") (pinfunction "4_4") (pintype "bidirectional"))
      (node (ref "JP2_4") (pin "2") (pinfunction "2_2") (pintype "passive"))
      (node (ref "JP2_5") (pin "4") (pinfunction "4_4") (pintype "bidirectional"))
      (node (ref "JP3_5") (pin "4") (pinfunction "4_4") (pintype "bidirectional"))
      (node (ref "JP4_5") (pin "4") (pinfunction "4_4") (pintype "bidirectional"))
      (node (ref "JP5_5") (pin "4") (pinfunction "4_4") (pintype "bidirectional"))
      (node (ref "R1_3") (pin "2") (pinfunction "2_2") (pintype "passive"))
      (node (ref "U1_3") (pin "5") (pinfunction "VDD_5") (pintype "power_in"))
      (node (ref "U1_4") (pin "1") (pinfunction "VIN_1") (pintype "bidirectional"))
      (node (ref "U1_4") (pin "3") (pinfunction "EN_3") (pintype "bidirectional"))
      (node (ref "U1_5") (pin "1") (pinfunction "VIN_1") (pintype "bidirectional"))
      (node (ref "U1_5") (pin "3") (pinfunction "EN_3") (pintype "bidirectional"))
      (node (ref "U2_3") (pin "1") (pinfunction "IN_1") (pintype "input"))
      (node (ref "U7_4") (pin "1") (pinfunction "VIN_1") (pintype "bidirectional"))
      (node (ref "U7_4") (pin "3") (pinfunction "EN_3") (pintype "bidirectional"))
    )
    (net (code "37") (name "VOUT") (class "Default")
      (node (ref "C2_3") (pin "1") (pinfunction "1_1") (pintype "passive"))
      (node (ref "J2_3") (pin "5") (pinfunction "5_5") (pintype "passive"))
      (node (ref "U2_3") (pin "5") (pinfunction "OUT_5") (pintype "passive"))
    )
    (net (code "38") (name "VRECT") (class "Default")
      (node (ref "C3_2") (pin "1") (pinfunction "1_1") (pintype "passive"))
      (node (ref "D1_2") (pin "C") (pinfunction "C_C") (pintype "passive"))
      (node (ref "D2_2") (pin "C") (pinfunction "C_C") (pintype "passive"))
      (node (ref "JP2_2") (pin "4") (pinfunction "4_4") (pintype "passive"))
      (node (ref "R4_2") (pin "1") (pinfunction "1_1") (pintype "passive"))
      (node (ref "U1_2") (pin "1") (pinfunction "IN_1") (pintype "input"))
      (node (ref "U1_2") (pin "3") (pinfunction "EN_3") (pintype "input"))
    )
    (net (code "39") (name "VSENSE") (class "Default")
      (node (ref "C1_1") (pin "1") (pinfunction "1_1") (pintype "passive"))
      (node (ref "JP3_1") (pin "3") (pinfunction "3_3") (pintype "bidirectional"))
      (node (ref "R1_1") (pin "1") (pinfunction "1_1") (pintype "passive"))
      (node (ref "R2_1") (pin "2") (pinfunction "2_2") (pintype "passive"))
    )
    (net (code "40") (name "unconnected-(J2_3-Pad1)") (class "Default")
      (node (ref "J2_3") (pin "1") (pinfunction "1_1") (pintype "passive"))
    )
    (net (code "41") (name "unconnected-(J2_3-Pad2)") (class "Default")
      (node (ref "J2_3") (pin "2") (pinfunction "2_2") (pintype "passive"))
    )
    (net (code "42") (name "unconnected-(J2_3-Pad3)") (class "Default")
      (node (ref "J2_3") (pin "3") (pinfunction "3_3") (pintype "passive"))
    )
    (net (code "43") (name "unconnected-(J2_3-Pad4)") (class "Default")
      (node (ref "J2_3") (pin "4") (pinfunction "4_4") (pintype "passive"))
    )
    (net (code "44") (name "unconnected-(J2_3-Pad6)") (class "Default")
      (node (ref "J2_3") (pin "6") (pinfunction "6_6") (pintype "passive"))
    )
    (net (code "45") (name "unconnected-(JP1_5-Pad3)") (class "Default")
      (node (ref "JP1_5") (pin "3") (pinfunction "3_3") (pintype "bidirectional"))
    )
    (net (code "46") (name "unconnected-(JP2_5-Pad3)") (class "Default")
      (node (ref "JP2_5") (pin "3") (pinfunction "3_3") (pintype "bidirectional"))
    )
    (net (code "47") (name "unconnected-(JP3_5-Pad3)") (class "Default")
      (node (ref "JP3_5") (pin "3") (pinfunction "3_3") (pintype "bidirectional"))
    )
    (net (code "48") (name "unconnected-(JP4_5-Pad3)") (class "Default")
      (node (ref "JP4_5") (pin "3") (pinfunction "3_3") (pintype "bidirectional"))
    )
    (net (code "49") (name "unconnected-(JP5_5-Pad3)") (class "Default")
      (node (ref "JP5_5") (pin "3") (pinfunction "3_3") (pintype "bidirectional"))
    )
    (net (code "50") (name "unconnected-(U1_4-PG-Pad6)") (class "Default")
      (node (ref "U1_4") (pin "6") (pinfunction "PG_6") (pintype "bidirectional"))
    )
    (net (code "51") (name "unconnected-(U2_3-NC-Pad4)") (class "Default")
      (node (ref "U2_3") (pin "4") (pinfunction "NC_4") (pintype "no_connect"))
    )
  )
)
